# PCB_AUTO-PUMP.net
KiCad netlist of a schematic drawn in Altium Designer
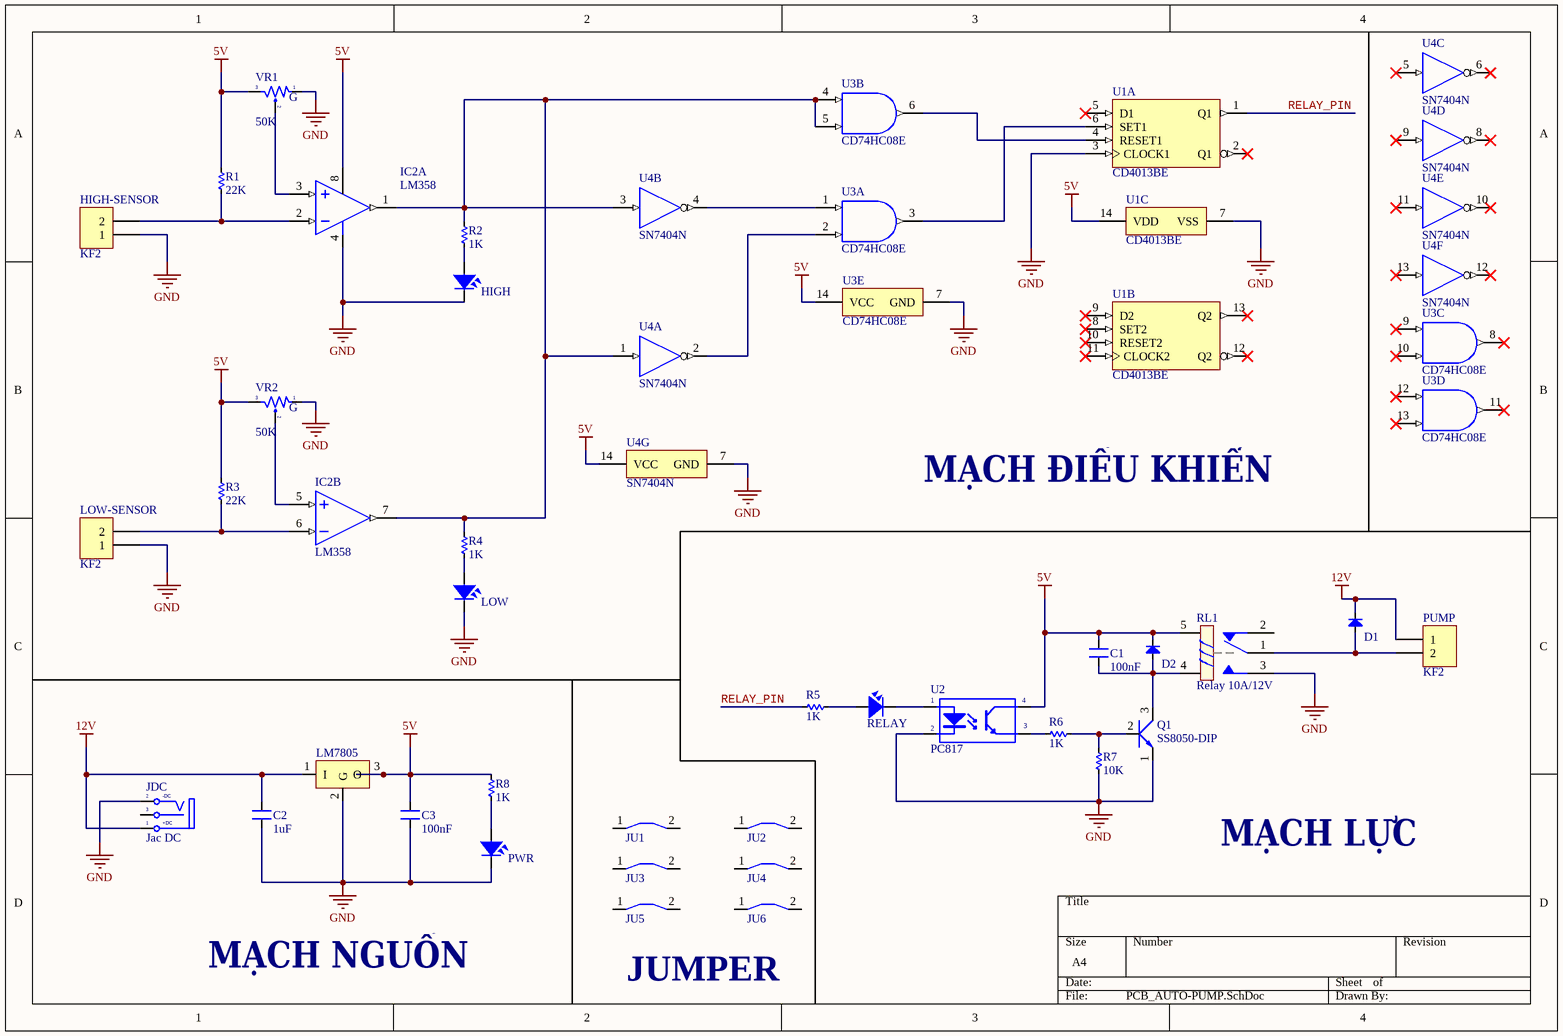
[diagram p0: PCB_AUTO-PUMP.SchDoc]

(export (version "E")
  (design (tool "Eeschema 10.0.6"))
  (components
    (comp (ref "C1") (value "100nF") (footprint "CN1.5") (libsource (lib "LIBRARY_MuaLinhKien") (part "CN")))
    (comp (ref "C2") (value "1uF") (footprint "CN1.5") (libsource (lib "LIBRARY_MuaLinhKien") (part "CN")))
    (comp (ref "C3") (value "100nF") (footprint "CN1.5") (libsource (lib "LIBRARY_MuaLinhKien") (part "CN")))
    (comp (ref "D1")
      (value "1N4007")
      (footprint "DIO-1A")
      (description "Default Diode")
      (fields (field (name "PUBLISHER") "Altium Limited"))
      (libsource (lib "LIBRARY_MuaLinhKien") (part "Diode"))
    )
    (comp (ref "D2")
      (value "1N4007")
      (footprint "DIO-1A")
      (description "Default Diode")
      (fields (field (name "PUBLISHER") "Altium Limited"))
      (libsource (lib "LIBRARY_MuaLinhKien") (part "Diode"))
    )
    (comp (ref "HIGH")
      (value "LED")
      (footprint "LED-5-Green")
      (description "LED Single colour Green and Red")
      (libsource (lib "LIBRARY_MuaLinhKien") (part "LED"))
    )
    (comp (ref "HIGH-SENSOR")
      (value "KF2")
      (footprint "KF2-5.08")
      (fields
        (field (name "MANUFACTURER") "Würth Elektronik eiSos GmbH")
        (field (name "PARTNO") "691103110002")
        (field (name "CREATED BY") "Karrer Zheng")
      )
      (libsource (lib "LIBRARY_MuaLinhKien") (part "KF2"))
    )
    (comp (ref "IC2")
      (value "LM358")
      (footprint "DIP8")
      (description "Low-Power Dual Operational Amplifier")
      (libsource (lib "LIBRARY_MuaLinhKien") (part "LM358"))
    )
    (comp (ref "JDC")
      (value "Jac DC")
      (footprint "DC0")
      (description "Jac DC input")
      (libsource (lib "LIBRARY_MuaLinhKien") (part "DCIN"))
    )
    (comp (ref "JU1")
      (value "JUMPER")
      (footprint "JUMPER 15MM")
      (libsource (lib "tunaSchlib") (part "JUMPER"))
    )
    (comp (ref "JU2")
      (value "JUMPER")
      (footprint "JUMPER 10MM")
      (libsource (lib "tunaSchlib") (part "JUMPER"))
    )
    (comp (ref "JU3")
      (value "JUMPER")
      (footprint "JUMPER 10MM")
      (libsource (lib "tunaSchlib") (part "JUMPER"))
    )
    (comp (ref "JU4")
      (value "JUMPER")
      (footprint "JUMPER 5MM")
      (libsource (lib "tunaSchlib") (part "JUMPER"))
    )
    (comp (ref "JU5")
      (value "JUMPER")
      (footprint "JUMPER 5MM")
      (libsource (lib "tunaSchlib") (part "JUMPER"))
    )
    (comp (ref "JU6")
      (value "JUMPER")
      (footprint "JUMPER 10MM")
      (libsource (lib "tunaSchlib") (part "JUMPER"))
    )
    (comp (ref "LM7805")
      (value "LM78xx")
      (footprint "TO220H1")
      (description "Positive Voltage Regulator")
      (fields (field (name "PUBLISHER") "Altium Limited"))
      (libsource (lib "LIBRARY_MuaLinhKien") (part "LM78xx"))
    )
    (comp (ref "LOW")
      (value "LED")
      (footprint "LED-5-Green")
      (description "LED Single colour Green and Red")
      (libsource (lib "LIBRARY_MuaLinhKien") (part "LED"))
    )
    (comp (ref "LOW-SENSOR")
      (value "KF2")
      (footprint "KF2-5.08")
      (fields
        (field (name "MANUFACTURER") "Würth Elektronik eiSos GmbH")
        (field (name "PARTNO") "691103110002")
        (field (name "CREATED BY") "Karrer Zheng")
      )
      (libsource (lib "LIBRARY_MuaLinhKien") (part "KF2"))
    )
    (comp (ref "PUMP")
      (value "KF2")
      (footprint "KF2-5.08")
      (fields
        (field (name "MANUFACTURER") "Würth Elektronik eiSos GmbH")
        (field (name "PARTNO") "691103110002")
        (field (name "CREATED BY") "Karrer Zheng")
      )
      (libsource (lib "") (part "KF2_1"))
    )
    (comp (ref "PWR")
      (value "LED")
      (footprint "LED-5-Green")
      (description "LED Single colour Green and Red")
      (libsource (lib "LIBRARY_MuaLinhKien") (part "LED"))
    )
    (comp (ref "Q1")
      (value "SS8050-DIP")
      (footprint "SS8050DIP")
      (description "NPN transistor through hole")
      (libsource (lib "Duc") (part "SS8050-DIP"))
    )
    (comp (ref "R1")
      (value "22K")
      (footprint "RES-1/4W")
      (description "Res")
      (fields
        (field (name "MANUFACTURER") "Generic Components")
        (field (name "PUBLISHER") "Altium Hobart Technology Centre")
      )
      (libsource (lib "LIBRARY_MuaLinhKien") (part "Res"))
    )
    (comp (ref "R2")
      (value "1K")
      (footprint "RES-1/4W")
      (description "Res")
      (fields
        (field (name "MANUFACTURER") "Generic Components")
        (field (name "PUBLISHER") "Altium Hobart Technology Centre")
      )
      (libsource (lib "LIBRARY_MuaLinhKien") (part "Res"))
    )
    (comp (ref "R3")
      (value "22K")
      (footprint "RES-1/4W")
      (description "Res")
      (fields
        (field (name "MANUFACTURER") "Generic Components")
        (field (name "PUBLISHER") "Altium Hobart Technology Centre")
      )
      (libsource (lib "LIBRARY_MuaLinhKien") (part "Res"))
    )
    (comp (ref "R4")
      (value "1K")
      (footprint "RES-1/4W")
      (description "Res")
      (fields
        (field (name "MANUFACTURER") "Generic Components")
        (field (name "PUBLISHER") "Altium Hobart Technology Centre")
      )
      (libsource (lib "LIBRARY_MuaLinhKien") (part "Res"))
    )
    (comp (ref "R5")
      (value "1K")
      (footprint "RES-1/4W")
      (description "Res")
      (fields
        (field (name "MANUFACTURER") "Generic Components")
        (field (name "PUBLISHER") "Altium Hobart Technology Centre")
      )
      (libsource (lib "LIBRARY_MuaLinhKien") (part "Res"))
    )
    (comp (ref "R6")
      (value "1K")
      (footprint "RES-1/4W")
      (description "Res")
      (fields
        (field (name "MANUFACTURER") "Generic Components")
        (field (name "PUBLISHER") "Altium Hobart Technology Centre")
      )
      (libsource (lib "LIBRARY_MuaLinhKien") (part "Res"))
    )
    (comp (ref "R7")
      (value "10K")
      (footprint "RES-1/4W")
      (description "Res")
      (fields
        (field (name "MANUFACTURER") "Generic Components")
        (field (name "PUBLISHER") "Altium Hobart Technology Centre")
      )
      (libsource (lib "LIBRARY_MuaLinhKien") (part "Res"))
    )
    (comp (ref "R8")
      (value "1K")
      (footprint "RES-1/4W")
      (description "Res")
      (fields
        (field (name "MANUFACTURER") "Generic Components")
        (field (name "PUBLISHER") "Altium Hobart Technology Centre")
      )
      (libsource (lib "LIBRARY_MuaLinhKien") (part "Res"))
    )
    (comp (ref "RELAY")
      (value "LED")
      (footprint "LED-5-Green")
      (description "LED Single colour Green and Red")
      (libsource (lib "LIBRARY_MuaLinhKien") (part "LED"))
    )
    (comp (ref "RL1")
      (value "Relay 10A/12V")
      (footprint "RELAY 5")
      (description "Relay SPDT,10A - 12VDC 5 Pin")
      (libsource (lib "LIBRARY_MuaLinhKien") (part "Relay 5"))
    )
    (comp (ref "U1")
      (value "CD4013BE")
      (footprint "N0014A")
      (description "CMOS Dual D-Type Flip Flop, N0014A, TUBE")
      (fields
        (field (name "GENERIC PART NUMBER") "CD4013B")
        (field (name "MANUFACTURER") "Texas Instruments")
      )
      (libsource (lib "Altium Content Vault") (part "TI-CD4013B-14"))
    )
    (comp (ref "U2")
      (value "PC817")
      (footprint "DIP4")
      (description "Single Opto")
      (libsource (lib "LIBRARY_MuaLinhKien") (part "PC817"))
    )
    (comp (ref "U3")
      (value "CD74HC08E")
      (footprint "N0014A")
      (description "High Speed CMOS Logic Quad 2-Input AND Gates, N0014A, TUBE")
      (fields
        (field (name "GENERIC PART NUMBER") "CD74HC08")
        (field (name "MANUFACTURER") "Texas Instruments")
      )
      (libsource (lib "Altium Content Vault") (part "TI-AND-4-2IN-14"))
    )
    (comp (ref "U4")
      (value "SN7404N")
      (footprint "N0014A")
      (description "Hex inverters, N0014A, TUBE")
      (fields (field (name "GENERIC PART NUMBER") "SN7404") (field (name "MANUFACTURER") "Texas Instruments"))
      (libsource (lib "Altium Content Vault") (part "TI-CD_SNX4XXXXXX4X_19A-14"))
    )
    (comp (ref "VR1")
      (value "50K")
      (footprint "VR-S2")
      (description "Var Resistor")
      (libsource (lib "LIBRARY_MuaLinhKien") (part "VR-S"))
    )
    (comp (ref "VR2")
      (value "50K")
      (footprint "VR-S2")
      (description "Var Resistor")
      (libsource (lib "LIBRARY_MuaLinhKien") (part "VR-S"))
    )
  )
  (nets
    (net (code "1") (name "/RELAY_PIN") (class "Default")
      (node (ref "R5") (pin "1") (pinfunction "1_1") (pintype "passive"))
      (node (ref "U1") (pin "1") (pinfunction "Q1_1") (pintype "output"))
    )
    (net (code "2") (name "5V") (class "Default")
      (node (ref "C1") (pin "1") (pinfunction "1_1") (pintype "passive"))
      (node (ref "C3") (pin "2") (pinfunction "2_2") (pintype "passive"))
      (node (ref "D2") (pin "2") (pinfunction "K_2") (pintype "passive"))
      (node (ref "IC2") (pin "8") (pinfunction "+V_8") (pintype "passive"))
      (node (ref "LM7805") (pin "3") (pinfunction "O_3") (pintype "power_in"))
      (node (ref "R1") (pin "1") (pinfunction "1_1") (pintype "passive"))
      (node (ref "R3") (pin "1") (pinfunction "1_1") (pintype "passive"))
      (node (ref "R8") (pin "2") (pinfunction "2_2") (pintype "passive"))
      (node (ref "RL1") (pin "5") (pinfunction "5_5") (pintype "passive"))
      (node (ref "U1") (pin "14") (pinfunction "VDD_14") (pintype "power_in"))
      (node (ref "U2") (pin "4") (pinfunction "C_4") (pintype "passive"))
      (node (ref "U3") (pin "14") (pinfunction "VCC_14") (pintype "power_in"))
      (node (ref "U4") (pin "14") (pinfunction "VCC_14") (pintype "power_in"))
      (node (ref "VR1") (pin "3") (pinfunction "3_3") (pintype "passive"))
      (node (ref "VR2") (pin "3") (pinfunction "3_3") (pintype "passive"))
    )
    (net (code "3") (name "12V") (class "Default")
      (node (ref "C2") (pin "2") (pinfunction "2_2") (pintype "passive"))
      (node (ref "D1") (pin "2") (pinfunction "K_2") (pintype "passive"))
      (node (ref "JDC") (pin "1") (pinfunction "T_1") (pintype "passive"))
      (node (ref "LM7805") (pin "1") (pinfunction "I_1") (pintype "power_in"))
      (node (ref "PUMP") (pin "1") (pinfunction "1_1") (pintype "passive"))
    )
    (net (code "4") (name "GND") (class "Default")
      (node (ref "C2") (pin "1") (pinfunction "1_1") (pintype "passive"))
      (node (ref "C3") (pin "1") (pinfunction "1_1") (pintype "passive"))
      (node (ref "HIGH") (pin "2") (pinfunction "2_2") (pintype "passive"))
      (node (ref "HIGH-SENSOR") (pin "1") (pinfunction "1_1") (pintype "passive"))
      (node (ref "IC2") (pin "4") (pinfunction "-V_4") (pintype "passive"))
      (node (ref "JDC") (pin "2") (pinfunction "TN_2") (pintype "passive"))
      (node (ref "LM7805") (pin "2") (pinfunction "G_2") (pintype "power_in"))
      (node (ref "LOW") (pin "2") (pinfunction "2_2") (pintype "passive"))
      (node (ref "LOW-SENSOR") (pin "1") (pinfunction "1_1") (pintype "passive"))
      (node (ref "PWR") (pin "2") (pinfunction "2_2") (pintype "passive"))
      (node (ref "Q1") (pin "1") (pinfunction "E_1") (pintype "passive"))
      (node (ref "R7") (pin "1") (pinfunction "1_1") (pintype "passive"))
      (node (ref "RL1") (pin "3") (pinfunction "3_3") (pintype "passive"))
      (node (ref "U1") (pin "3") (pinfunction "CLOCK1_3") (pintype "input"))
      (node (ref "U1") (pin "7") (pinfunction "VSS_7") (pintype "power_in"))
      (node (ref "U2") (pin "2") (pinfunction "K_2") (pintype "passive"))
      (node (ref "U3") (pin "7") (pinfunction "GND_7") (pintype "power_in"))
      (node (ref "U4") (pin "7") (pinfunction "GND_7") (pintype "power_in"))
      (node (ref "VR1") (pin "1") (pinfunction "1_1") (pintype "passive"))
      (node (ref "VR2") (pin "1") (pinfunction "1_1") (pintype "passive"))
    )
    (net (code "5") (name "Net-(D1-A)") (class "Default")
      (node (ref "D1") (pin "1") (pinfunction "A_1") (pintype "passive"))
      (node (ref "PUMP") (pin "2") (pinfunction "2_2") (pintype "passive"))
      (node (ref "RL1") (pin "1") (pinfunction "1_1") (pintype "passive"))
    )
    (net (code "6") (name "Net-(D2-A)") (class "Default")
      (node (ref "C1") (pin "2") (pinfunction "2_2") (pintype "passive"))
      (node (ref "D2") (pin "1") (pinfunction "A_1") (pintype "passive"))
      (node (ref "Q1") (pin "3") (pinfunction "C_3") (pintype "passive"))
      (node (ref "RL1") (pin "4") (pinfunction "4_4") (pintype "passive"))
    )
    (net (code "7") (name "Net-(HIGH-Pad1)") (class "Default")
      (node (ref "HIGH") (pin "1") (pinfunction "1_1") (pintype "passive"))
      (node (ref "R2") (pin "1") (pinfunction "1_1") (pintype "passive"))
    )
    (net (code "8") (name "Net-(IC2A-IN+)") (class "Default")
      (node (ref "IC2") (pin "3") (pinfunction "IN+_3") (pintype "input"))
      (node (ref "VR1") (pin "2") (pinfunction "2_2") (pintype "passive"))
    )
    (net (code "9") (name "Net-(IC2A-IN-)") (class "Default")
      (node (ref "HIGH-SENSOR") (pin "2") (pinfunction "2_2") (pintype "passive"))
      (node (ref "IC2") (pin "2") (pinfunction "IN-_2") (pintype "input"))
      (node (ref "R1") (pin "2") (pinfunction "2_2") (pintype "passive"))
    )
    (net (code "10") (name "Net-(IC2A-OUT)") (class "Default")
      (node (ref "IC2") (pin "1") (pinfunction "OUT_1") (pintype "output"))
      (node (ref "IC2") (pin "7") (pinfunction "OUT_7") (pintype "output"))
      (node (ref "R2") (pin "2") (pinfunction "2_2") (pintype "passive"))
      (node (ref "R4") (pin "2") (pinfunction "2_2") (pintype "passive"))
      (node (ref "U3") (pin "4") (pinfunction "2A_4") (pintype "input"))
      (node (ref "U3") (pin "5") (pinfunction "2B_5") (pintype "input"))
      (node (ref "U4") (pin "1") (pinfunction "1A_1") (pintype "input"))
      (node (ref "U4") (pin "3") (pinfunction "2A_3") (pintype "input"))
    )
    (net (code "11") (name "Net-(IC2B-IN+)") (class "Default")
      (node (ref "IC2") (pin "5") (pinfunction "IN+_5") (pintype "input"))
      (node (ref "VR2") (pin "2") (pinfunction "2_2") (pintype "passive"))
    )
    (net (code "12") (name "Net-(IC2B-IN-)") (class "Default")
      (node (ref "IC2") (pin "6") (pinfunction "IN-_6") (pintype "input"))
      (node (ref "LOW-SENSOR") (pin "2") (pinfunction "2_2") (pintype "passive"))
      (node (ref "R3") (pin "2") (pinfunction "2_2") (pintype "passive"))
    )
    (net (code "13") (name "Net-(LOW-Pad1)") (class "Default")
      (node (ref "LOW") (pin "1") (pinfunction "1_1") (pintype "passive"))
      (node (ref "R4") (pin "1") (pinfunction "1_1") (pintype "passive"))
    )
    (net (code "14") (name "Net-(PWR-Pad1)") (class "Default")
      (node (ref "PWR") (pin "1") (pinfunction "1_1") (pintype "passive"))
      (node (ref "R8") (pin "1") (pinfunction "1_1") (pintype "passive"))
    )
    (net (code "15") (name "Net-(Q1-B)") (class "Default")
      (node (ref "Q1") (pin "2") (pinfunction "B_2") (pintype "passive"))
      (node (ref "R6") (pin "2") (pinfunction "2_2") (pintype "passive"))
      (node (ref "R7") (pin "2") (pinfunction "2_2") (pintype "passive"))
    )
    (net (code "16") (name "Net-(R5-Pad2)") (class "Default")
      (node (ref "R5") (pin "2") (pinfunction "2_2") (pintype "passive"))
      (node (ref "RELAY") (pin "1") (pinfunction "1_1") (pintype "passive"))
    )
    (net (code "17") (name "Net-(U1A-RESET1)") (class "Default")
      (node (ref "U1") (pin "4") (pinfunction "RESET1_4") (pintype "input"))
      (node (ref "U3") (pin "6") (pinfunction "2Y_6") (pintype "output"))
    )
    (net (code "18") (name "Net-(U1A-SET1)") (class "Default")
      (node (ref "U1") (pin "6") (pinfunction "SET1_6") (pintype "input"))
      (node (ref "U3") (pin "3") (pinfunction "1Y_3") (pintype "output"))
    )
    (net (code "19") (name "Net-(U2-A)") (class "Default")
      (node (ref "RELAY") (pin "2") (pinfunction "2_2") (pintype "passive"))
      (node (ref "U2") (pin "1") (pinfunction "A_1") (pintype "passive"))
    )
    (net (code "20") (name "Net-(U2-E)") (class "Default")
      (node (ref "R6") (pin "1") (pinfunction "1_1") (pintype "passive"))
      (node (ref "U2") (pin "3") (pinfunction "E_3") (pintype "passive"))
    )
    (net (code "21") (name "Net-(U3A-1A)") (class "Default")
      (node (ref "U3") (pin "1") (pinfunction "1A_1") (pintype "input"))
      (node (ref "U4") (pin "4") (pinfunction "~{2Y}_4") (pintype "output"))
    )
    (net (code "22") (name "Net-(U3A-1B)") (class "Default")
      (node (ref "U3") (pin "2") (pinfunction "1B_2") (pintype "input"))
      (node (ref "U4") (pin "2") (pinfunction "~{1Y}_2") (pintype "output"))
    )
    (net (code "23") (name "unconnected-(JDC-S-Pad3)") (class "Default")
      (node (ref "JDC") (pin "3") (pinfunction "S_3") (pintype "power_in"))
    )
    (net (code "24") (name "unconnected-(JU1-Pad1)") (class "Default")
      (node (ref "JU1") (pin "1") (pinfunction "1_1") (pintype "power_in"))
    )
    (net (code "25") (name "unconnected-(JU1-Pad2)") (class "Default")
      (node (ref "JU1") (pin "2") (pinfunction "2_2") (pintype "power_in"))
    )
    (net (code "26") (name "unconnected-(JU2-Pad1)") (class "Default")
      (node (ref "JU2") (pin "1") (pinfunction "1_1") (pintype "power_in"))
    )
    (net (code "27") (name "unconnected-(JU2-Pad2)") (class "Default")
      (node (ref "JU2") (pin "2") (pinfunction "2_2") (pintype "power_in"))
    )
    (net (code "28") (name "unconnected-(JU3-Pad1)") (class "Default")
      (node (ref "JU3") (pin "1") (pinfunction "1_1") (pintype "power_in"))
    )
    (net (code "29") (name "unconnected-(JU3-Pad2)") (class "Default")
      (node (ref "JU3") (pin "2") (pinfunction "2_2") (pintype "power_in"))
    )
    (net (code "30") (name "unconnected-(JU4-Pad1)") (class "Default")
      (node (ref "JU4") (pin "1") (pinfunction "1_1") (pintype "power_in"))
    )
    (net (code "31") (name "unconnected-(JU4-Pad2)") (class "Default")
      (node (ref "JU4") (pin "2") (pinfunction "2_2") (pintype "power_in"))
    )
    (net (code "32") (name "unconnected-(JU5-Pad1)") (class "Default")
      (node (ref "JU5") (pin "1") (pinfunction "1_1") (pintype "power_in"))
    )
    (net (code "33") (name "unconnected-(JU5-Pad2)") (class "Default")
      (node (ref "JU5") (pin "2") (pinfunction "2_2") (pintype "power_in"))
    )
    (net (code "34") (name "unconnected-(JU6-Pad1)") (class "Default")
      (node (ref "JU6") (pin "1") (pinfunction "1_1") (pintype "power_in"))
    )
    (net (code "35") (name "unconnected-(JU6-Pad2)") (class "Default")
      (node (ref "JU6") (pin "2") (pinfunction "2_2") (pintype "power_in"))
    )
    (net (code "36") (name "unconnected-(RL1-Pad2)") (class "Default")
      (node (ref "RL1") (pin "2") (pinfunction "2_2") (pintype "passive"))
    )
    (net (code "37") (name "unconnected-(U1A-D1-Pad5)") (class "Default")
      (node (ref "U1") (pin "5") (pinfunction "D1_5") (pintype "input+no_connect"))
    )
    (net (code "38") (name "unconnected-(U1A-Q1-Pad2)") (class "Default")
      (node (ref "U1") (pin "2") (pinfunction "Q1_2") (pintype "output+no_connect"))
    )
    (net (code "39") (name "unconnected-(U1B-CLOCK2-Pad11)") (class "Default")
      (node (ref "U1") (pin "11") (pinfunction "CLOCK2_11") (pintype "input+no_connect"))
    )
    (net (code "40") (name "unconnected-(U1B-D2-Pad9)") (class "Default")
      (node (ref "U1") (pin "9") (pinfunction "D2_9") (pintype "input+no_connect"))
    )
    (net (code "41") (name "unconnected-(U1B-Q2-Pad12)") (class "Default")
      (node (ref "U1") (pin "12") (pinfunction "Q2_12") (pintype "output+no_connect"))
    )
    (net (code "42") (name "unconnected-(U1B-Q2-Pad13)") (class "Default")
      (node (ref "U1") (pin "13") (pinfunction "Q2_13") (pintype "output+no_connect"))
    )
    (net (code "43") (name "unconnected-(U1B-RESET2-Pad10)") (class "Default")
      (node (ref "U1") (pin "10") (pinfunction "RESET2_10") (pintype "input+no_connect"))
    )
    (net (code "44") (name "unconnected-(U1B-SET2-Pad8)") (class "Default")
      (node (ref "U1") (pin "8") (pinfunction "SET2_8") (pintype "input+no_connect"))
    )
    (net (code "45") (name "unconnected-(U3C-3A-Pad9)") (class "Default")
      (node (ref "U3") (pin "9") (pinfunction "3A_9") (pintype "input+no_connect"))
    )
    (net (code "46") (name "unconnected-(U3C-3B-Pad10)") (class "Default")
      (node (ref "U3") (pin "10") (pinfunction "3B_10") (pintype "input+no_connect"))
    )
    (net (code "47") (name "unconnected-(U3C-3Y-Pad8)") (class "Default")
      (node (ref "U3") (pin "8") (pinfunction "3Y_8") (pintype "output+no_connect"))
    )
    (net (code "48") (name "unconnected-(U3D-4A-Pad12)") (class "Default")
      (node (ref "U3") (pin "12") (pinfunction "4A_12") (pintype "input+no_connect"))
    )
    (net (code "49") (name "unconnected-(U3D-4B-Pad13)") (class "Default")
      (node (ref "U3") (pin "13") (pinfunction "4B_13") (pintype "input+no_connect"))
    )
    (net (code "50") (name "unconnected-(U3D-4Y-Pad11)") (class "Default")
      (node (ref "U3") (pin "11") (pinfunction "4Y_11") (pintype "output+no_connect"))
    )
    (net (code "51") (name "unconnected-(U4C-3A-Pad5)") (class "Default")
      (node (ref "U4") (pin "5") (pinfunction "3A_5") (pintype "input+no_connect"))
    )
    (net (code "52") (name "unconnected-(U4C-~{3Y}-Pad6)") (class "Default")
      (node (ref "U4") (pin "6") (pinfunction "~{3Y}_6") (pintype "output+no_connect"))
    )
    (net (code "53") (name "unconnected-(U4D-4A-Pad9)") (class "Default")
      (node (ref "U4") (pin "9") (pinfunction "4A_9") (pintype "input+no_connect"))
    )
    (net (code "54") (name "unconnected-(U4D-~{4Y}-Pad8)") (class "Default")
      (node (ref "U4") (pin "8") (pinfunction "~{4Y}_8") (pintype "output+no_connect"))
    )
    (net (code "55") (name "unconnected-(U4E-5A-Pad11)") (class "Default")
      (node (ref "U4") (pin "11") (pinfunction "5A_11") (pintype "input+no_connect"))
    )
    (net (code "56") (name "unconnected-(U4E-~{5Y}-Pad10)") (class "Default")
      (node (ref "U4") (pin "10") (pinfunction "~{5Y}_10") (pintype "output+no_connect"))
    )
    (net (code "57") (name "unconnected-(U4F-6A-Pad13)") (class "Default")
      (node (ref "U4") (pin "13") (pinfunction "6A_13") (pintype "input+no_connect"))
    )
    (net (code "58") (name "unconnected-(U4F-~{6Y}-Pad12)") (class "Default")
      (node (ref "U4") (pin "12") (pinfunction "~{6Y}_12") (pintype "output+no_connect"))
    )
  )
)
